# Test_Board.net
KiCad netlist of a schematic drawn in EAGLE
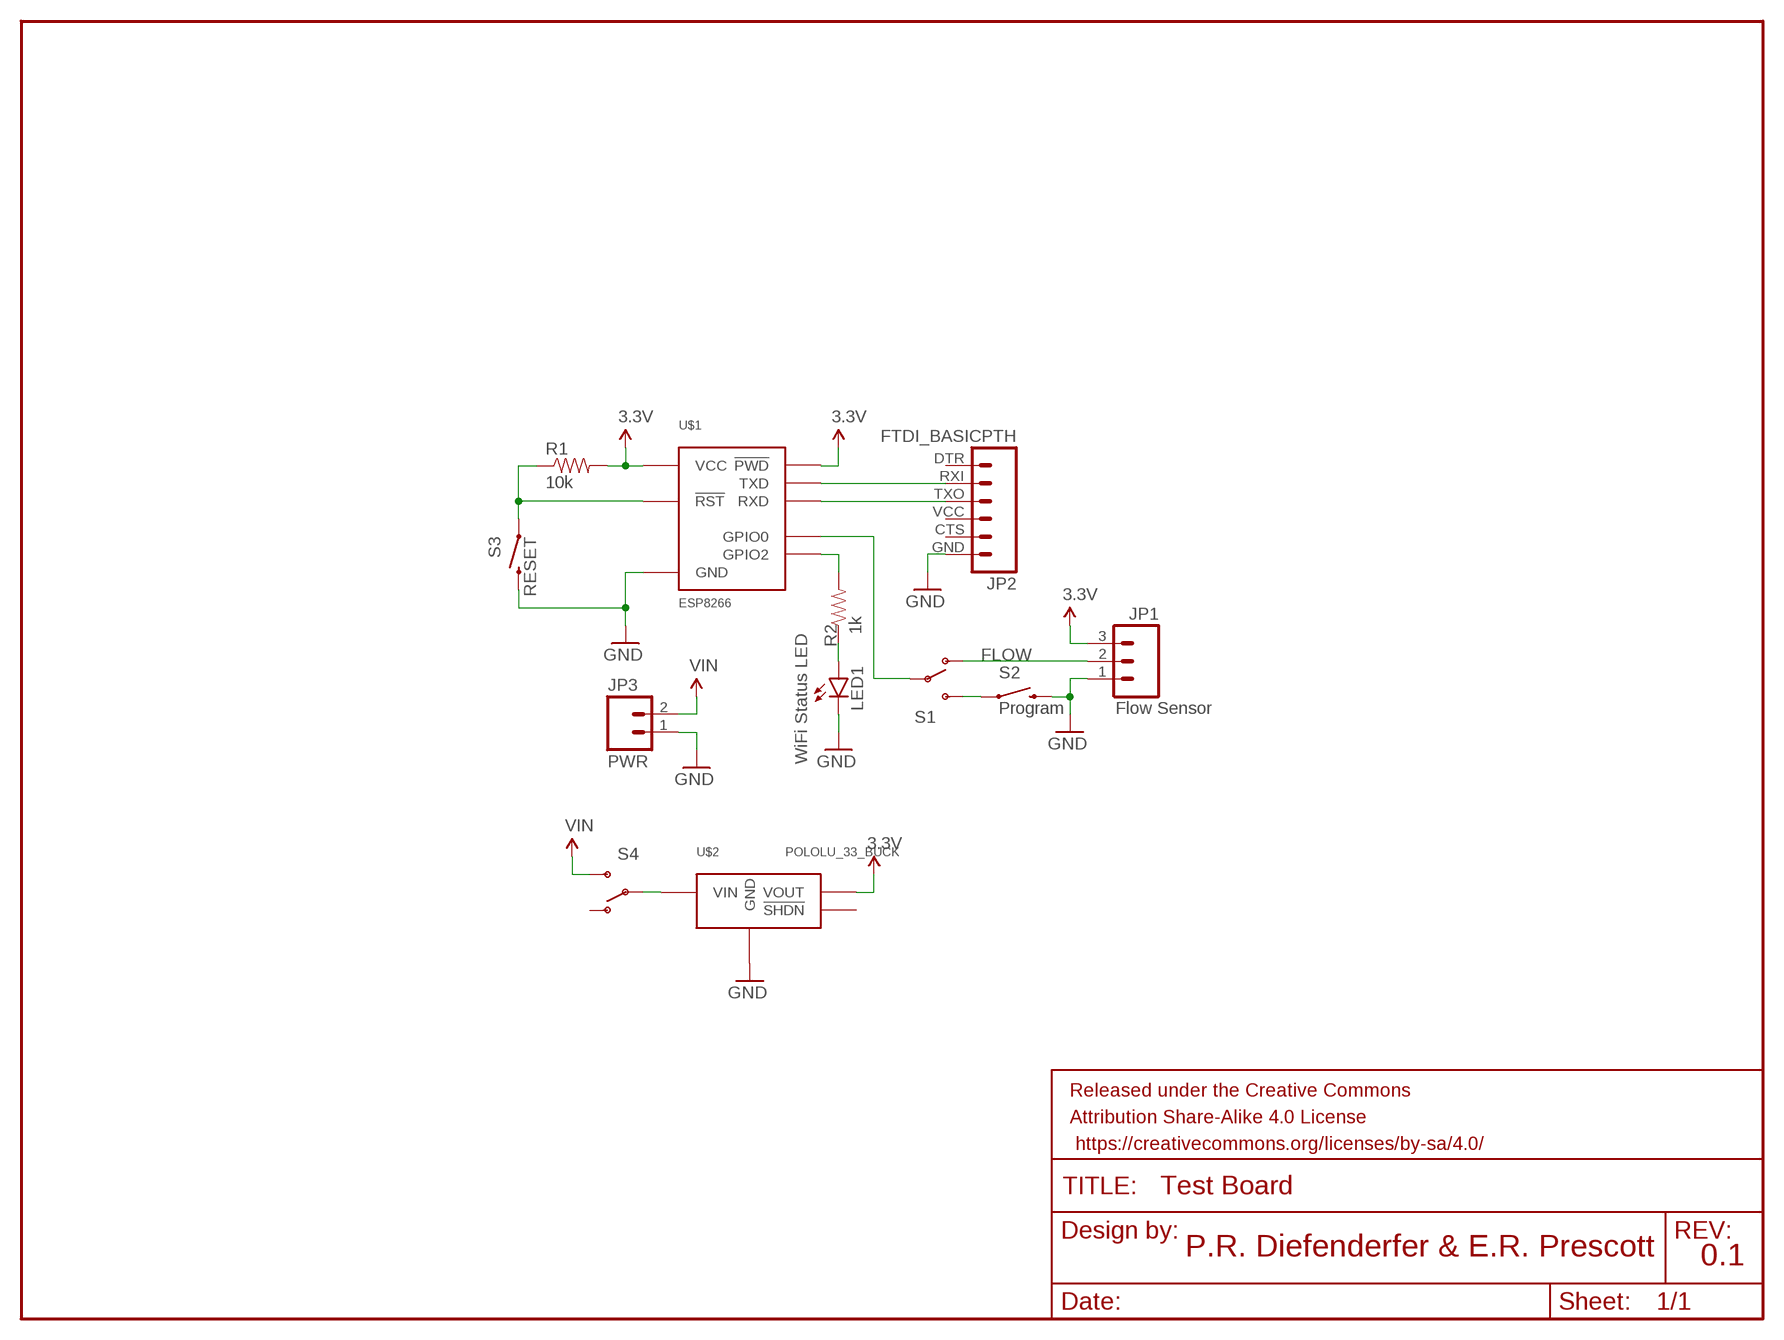
[diagram p0: schematic, sheet 1]

(export (version "E")
  (design (tool "Eeschema 10.0.6"))
  (components
    (comp (ref "FRAME1")
      (value "FRAME-LETTER")
      (footprint "eagle-import:CREATIVE_COMMONS")
      (libsource (lib "eagle-import") (part "FRAME-LETTER"))
    )
    (comp (ref "JP1")
      (value "Flow Sensor")
      (footprint "eagle-import:1X03_LOCK")
      (libsource (lib "eagle-import") (part "M03LOCK"))
    )
    (comp (ref "JP2")
      (value "FTDI_BASICPTH")
      (footprint "eagle-import:FTDI_BASIC")
      (libsource (lib "eagle-import") (part "FTDI_BASICPTH"))
    )
    (comp (ref "JP3")
      (value "PWR")
      (footprint "eagle-import:1X02_LOCK")
      (libsource (lib "eagle-import") (part "M02LOCK"))
    )
    (comp (ref "LED1")
      (value "WiFi Status LED")
      (footprint "eagle-import:LED3MM-NS")
      (libsource (lib "eagle-import") (part "LED-3MM-NO_SILK"))
    )
    (comp (ref "R1")
      (value "10k")
      (footprint "eagle-import:AXIAL-0.3")
      (libsource (lib "eagle-import") (part "RESISTORAXIAL-0.3"))
    )
    (comp (ref "R2")
      (value "1k")
      (footprint "eagle-import:AXIAL-0.3")
      (libsource (lib "eagle-import") (part "RESISTORAXIAL-0.3"))
    )
    (comp (ref "S1")
      (value "SWITCH-SPDTPTH")
      (footprint "eagle-import:SWITCH-SPDT")
      (libsource (lib "eagle-import") (part "SWITCH-SPDTPTH"))
    )
    (comp (ref "S2")
      (value "Program")
      (footprint "eagle-import:TACTILE-PTH")
      (libsource (lib "eagle-import") (part "SWITCH-MOMENTARY-2PTH"))
    )
    (comp (ref "S3")
      (value "RESET")
      (footprint "eagle-import:TACTILE-PTH")
      (libsource (lib "eagle-import") (part "SWITCH-MOMENTARY-2PTH"))
    )
    (comp (ref "S4")
      (value "SWITCH-SPDTPTH")
      (footprint "eagle-import:SWITCH-SPDT")
      (libsource (lib "eagle-import") (part "SWITCH-SPDTPTH"))
    )
    (comp (ref "U$1")
      (value "ESP8266")
      (footprint "eagle-import:2X4_LOCK")
      (libsource (lib "eagle-import") (part "ESP8266_R3"))
    )
    (comp (ref "U$2")
      (value "POLOLU_33_BUCK")
      (footprint "eagle-import:1X4_LOCK")
      (libsource (lib "eagle-import") (part "POLOLU_33_BUCK"))
    )
  )
  (nets
    (net (code "1") (name "/FLOW") (class "Default")
      (node (ref "JP1") (pin "2") (pinfunction "2_2") (pintype "passive"))
      (node (ref "S1") (pin "1") (pinfunction "O_1") (pintype "passive"))
    )
    (net (code "2") (name "3.3V") (class "Default")
      (node (ref "JP1") (pin "3") (pinfunction "3_3") (pintype "passive"))
      (node (ref "R1") (pin "P$2") (pinfunction "2_P$2") (pintype "passive"))
      (node (ref "U$1") (pin "CH_PD") (pinfunction "~{PWD}_CH_PD") (pintype "bidirectional"))
      (node (ref "U$1") (pin "VCC") (pinfunction "VCC_VCC") (pintype "bidirectional"))
      (node (ref "U$2") (pin "VOUT") (pinfunction "VOUT_VOUT") (pintype "bidirectional"))
    )
    (net (code "3") (name "GND") (class "Default")
      (node (ref "JP1") (pin "1") (pinfunction "1_1") (pintype "passive"))
      (node (ref "JP2") (pin "GND") (pinfunction "6_GND") (pintype "passive"))
      (node (ref "JP3") (pin "1") (pinfunction "1_1") (pintype "passive"))
      (node (ref "LED1") (pin "K") (pinfunction "C_K") (pintype "passive"))
      (node (ref "S2") (pin "3") (pinfunction "2_3") (pintype "passive"))
      (node (ref "S3") (pin "3") (pinfunction "2_3") (pintype "passive"))
      (node (ref "U$1") (pin "GND") (pinfunction "GND_GND") (pintype "bidirectional"))
      (node (ref "U$2") (pin "GND") (pinfunction "GND_GND") (pintype "bidirectional"))
    )
    (net (code "4") (name "Net-(JP2-2)") (class "Default")
      (node (ref "JP2") (pin "RXI") (pinfunction "2_RXI") (pintype "passive"))
      (node (ref "U$1") (pin "TXD") (pinfunction "TXD_TXD") (pintype "bidirectional"))
    )
    (net (code "5") (name "Net-(JP2-3)") (class "Default")
      (node (ref "JP2") (pin "TXO") (pinfunction "3_TXO") (pintype "passive"))
      (node (ref "U$1") (pin "RXD") (pinfunction "RXD_RXD") (pintype "bidirectional"))
    )
    (net (code "6") (name "Net-(R1-1)") (class "Default")
      (node (ref "R1") (pin "P$1") (pinfunction "1_P$1") (pintype "passive"))
      (node (ref "S3") (pin "1") (pinfunction "1_1") (pintype "passive"))
      (node (ref "U$1") (pin "RST") (pinfunction "~{RST}_RST") (pintype "bidirectional"))
    )
    (net (code "7") (name "Net-(R2-1)") (class "Default")
      (node (ref "LED1") (pin "A") (pinfunction "A_A") (pintype "passive"))
      (node (ref "R2") (pin "P$1") (pinfunction "1_P$1") (pintype "passive"))
    )
    (net (code "8") (name "Net-(R2-2)") (class "Default")
      (node (ref "R2") (pin "P$2") (pinfunction "2_P$2") (pintype "passive"))
      (node (ref "U$1") (pin "GPIO2") (pinfunction "GPIO2_GPIO2") (pintype "bidirectional"))
    )
    (net (code "9") (name "Net-(S1-P)") (class "Default")
      (node (ref "S1") (pin "2") (pinfunction "P_2") (pintype "passive"))
      (node (ref "U$1") (pin "GPIO0") (pinfunction "GPIO0_GPIO0") (pintype "bidirectional"))
    )
    (net (code "10") (name "Net-(S1-S)") (class "Default")
      (node (ref "S1") (pin "3") (pinfunction "S_3") (pintype "passive"))
      (node (ref "S2") (pin "1") (pinfunction "1_1") (pintype "passive"))
    )
    (net (code "11") (name "Net-(S4-P)") (class "Default")
      (node (ref "S4") (pin "2") (pinfunction "P_2") (pintype "passive"))
      (node (ref "U$2") (pin "VIN") (pinfunction "VIN_VIN") (pintype "bidirectional"))
    )
    (net (code "12") (name "VIN") (class "Default")
      (node (ref "JP3") (pin "2") (pinfunction "2_2") (pintype "passive"))
      (node (ref "S4") (pin "3") (pinfunction "S_3") (pintype "passive"))
    )
    (net (code "13") (name "unconnected-(JP2-1-PadDTR)") (class "Default")
      (node (ref "JP2") (pin "DTR") (pinfunction "1_DTR") (pintype "passive"))
    )
    (net (code "14") (name "unconnected-(JP2-4-PadVCC)") (class "Default")
      (node (ref "JP2") (pin "VCC") (pinfunction "4_VCC") (pintype "passive"))
    )
    (net (code "15") (name "unconnected-(JP2-5-PadCTS)") (class "Default")
      (node (ref "JP2") (pin "CTS") (pinfunction "5_CTS") (pintype "passive"))
    )
    (net (code "16") (name "unconnected-(S4-O-Pad1)") (class "Default")
      (node (ref "S4") (pin "1") (pinfunction "O_1") (pintype "passive"))
    )
    (net (code "17") (name "unconnected-(U$2-~{SHDN}-Pad!SHDN)") (class "Default")
      (node (ref "U$2") (pin "!SHDN") (pinfunction "~{SHDN}_!SHDN") (pintype "bidirectional"))
    )
  )
)
